# gigafoc.net
KiCad netlist of a schematic drawn in EAGLE
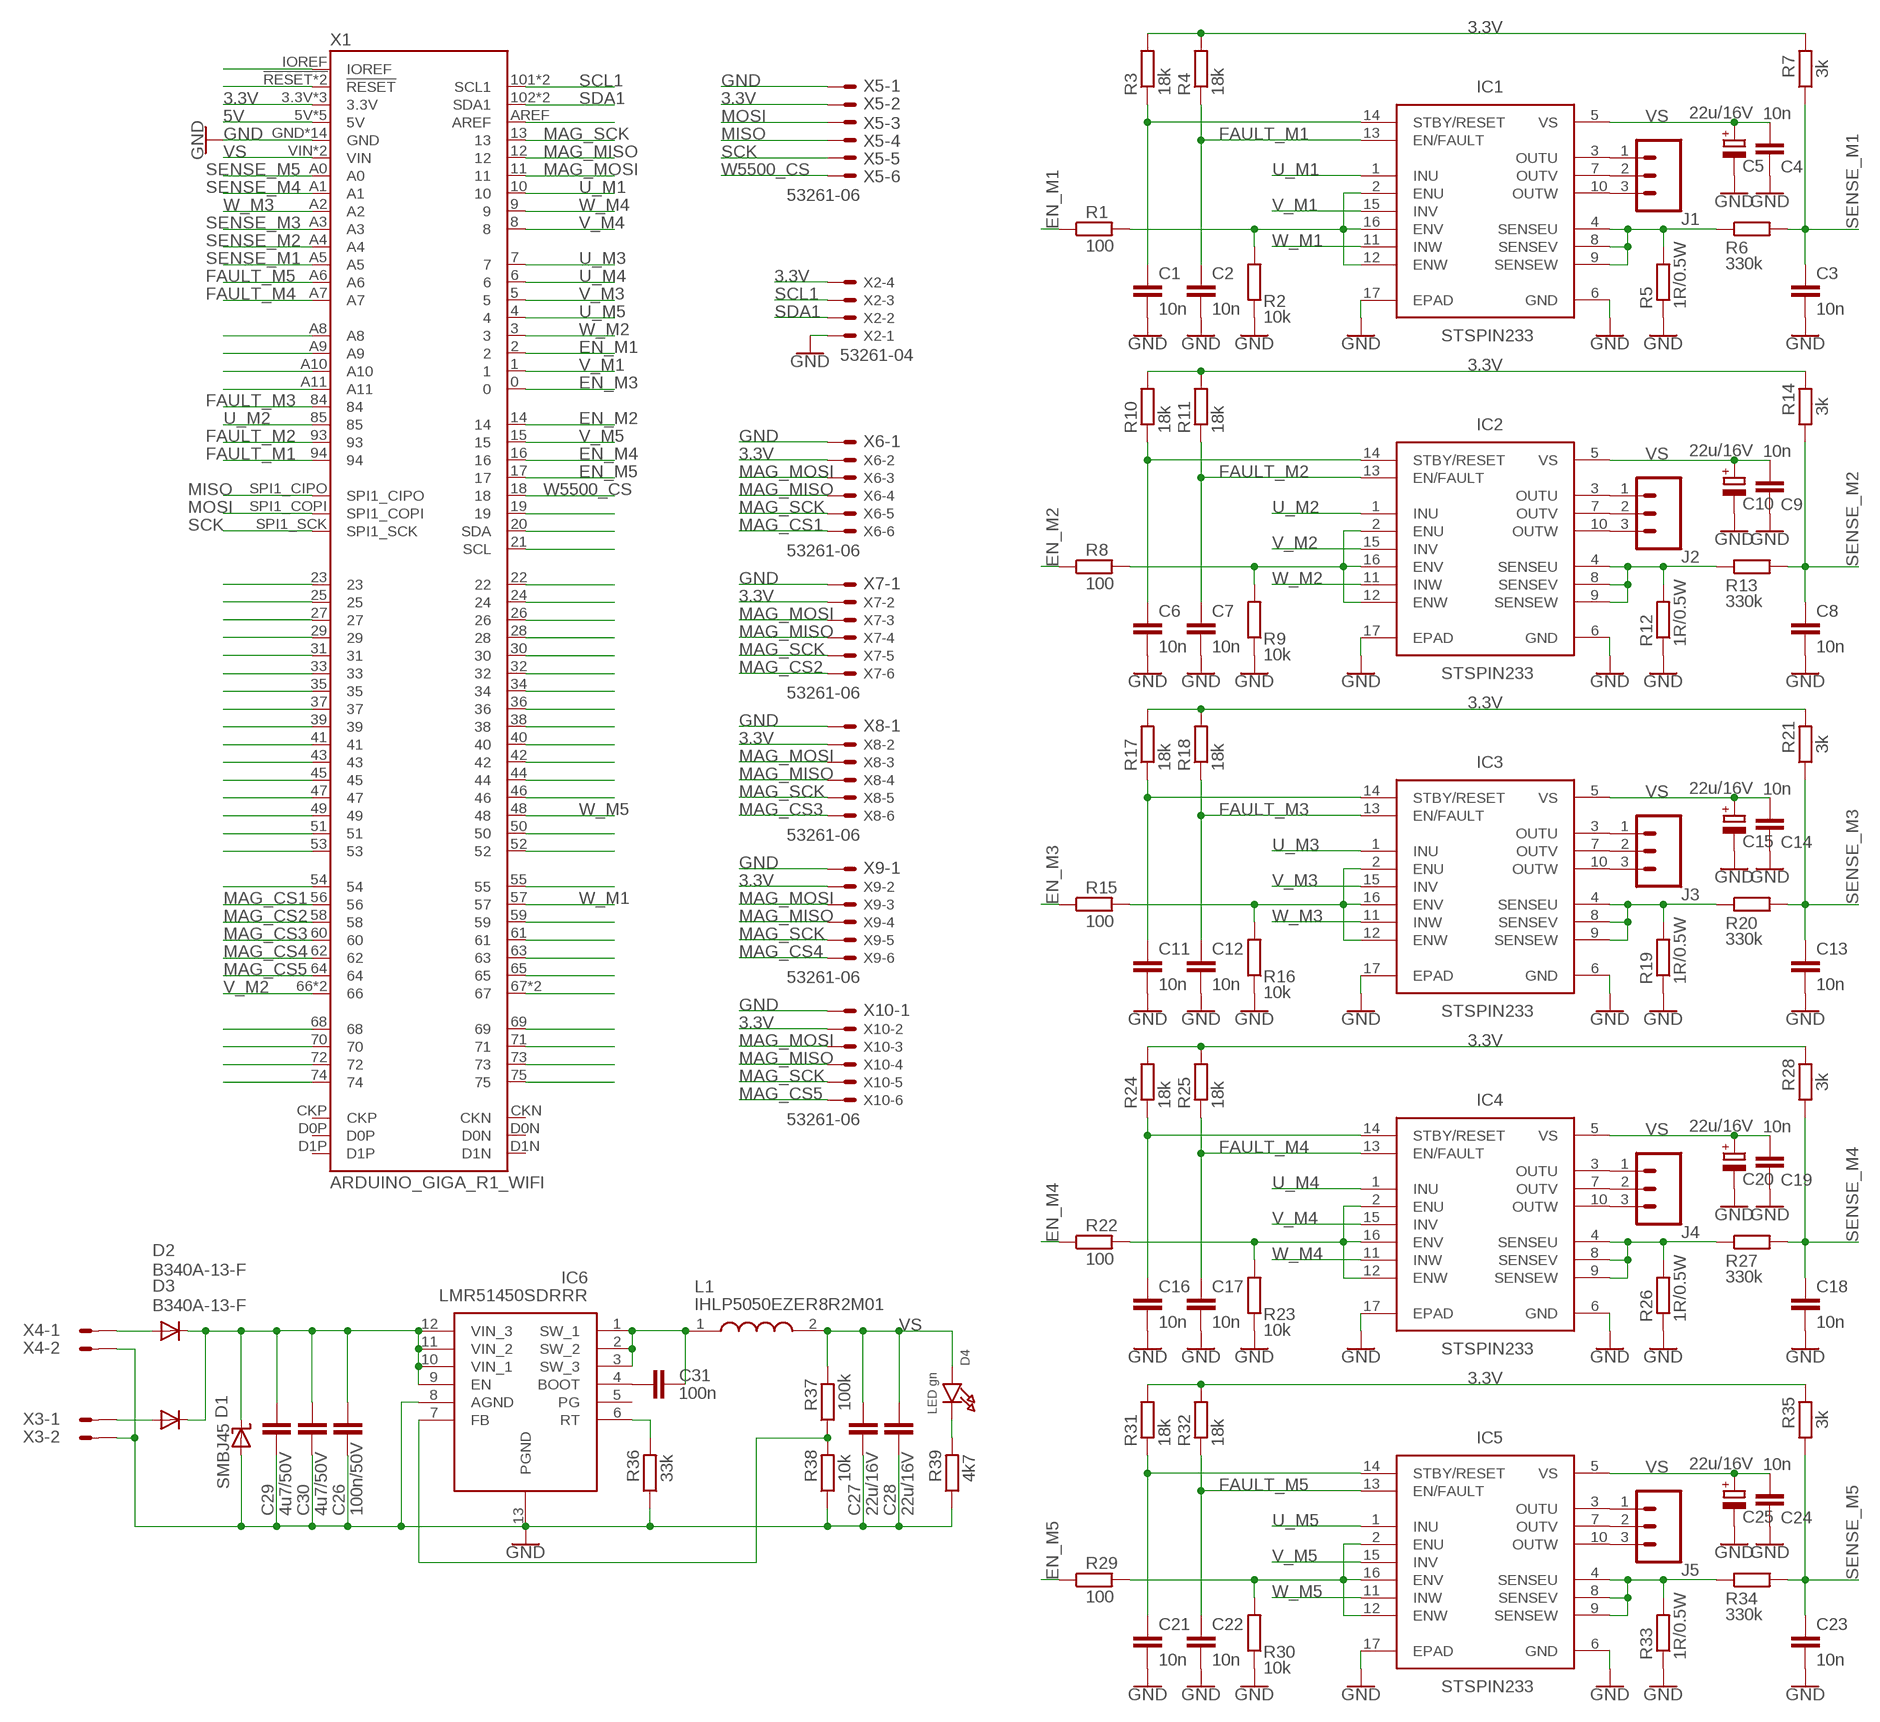
[diagram p0: schematic, sheet 1]

(export (version "E")
  (design (tool "Eeschema 10.0.6"))
  (components
    (comp (ref "C1")
      (value "10n")
      (footprint "eagle-import:C0603")
      (libsource (lib "eagle-import") (part "C-EUC0603"))
    )
    (comp (ref "C2")
      (value "10n")
      (footprint "eagle-import:C0603")
      (libsource (lib "eagle-import") (part "C-EUC0603"))
    )
    (comp (ref "C3")
      (value "10n")
      (footprint "eagle-import:C0603")
      (libsource (lib "eagle-import") (part "C-EUC0603"))
    )
    (comp (ref "C4")
      (value "10n")
      (footprint "eagle-import:C0603")
      (libsource (lib "eagle-import") (part "C-EUC0603"))
    )
    (comp (ref "C5")
      (value "22u/16V")
      (footprint "eagle-import:SMC_B")
      (libsource (lib "eagle-import") (part "CPOL-EUSMCB"))
    )
    (comp (ref "C6")
      (value "10n")
      (footprint "eagle-import:C0603")
      (libsource (lib "eagle-import") (part "C-EUC0603"))
    )
    (comp (ref "C7")
      (value "10n")
      (footprint "eagle-import:C0603")
      (libsource (lib "eagle-import") (part "C-EUC0603"))
    )
    (comp (ref "C8")
      (value "10n")
      (footprint "eagle-import:C0603")
      (libsource (lib "eagle-import") (part "C-EUC0603"))
    )
    (comp (ref "C9")
      (value "10n")
      (footprint "eagle-import:C0603")
      (libsource (lib "eagle-import") (part "C-EUC0603"))
    )
    (comp (ref "C10")
      (value "22u/16V")
      (footprint "eagle-import:SMC_B")
      (libsource (lib "eagle-import") (part "CPOL-EUSMCB"))
    )
    (comp (ref "C11")
      (value "10n")
      (footprint "eagle-import:C0603")
      (libsource (lib "eagle-import") (part "C-EUC0603"))
    )
    (comp (ref "C12")
      (value "10n")
      (footprint "eagle-import:C0603")
      (libsource (lib "eagle-import") (part "C-EUC0603"))
    )
    (comp (ref "C13")
      (value "10n")
      (footprint "eagle-import:C0603")
      (libsource (lib "eagle-import") (part "C-EUC0603"))
    )
    (comp (ref "C14")
      (value "10n")
      (footprint "eagle-import:C0603")
      (libsource (lib "eagle-import") (part "C-EUC0603"))
    )
    (comp (ref "C15")
      (value "22u/16V")
      (footprint "eagle-import:SMC_B")
      (libsource (lib "eagle-import") (part "CPOL-EUSMCB"))
    )
    (comp (ref "C16")
      (value "10n")
      (footprint "eagle-import:C0603")
      (libsource (lib "eagle-import") (part "C-EUC0603"))
    )
    (comp (ref "C17")
      (value "10n")
      (footprint "eagle-import:C0603")
      (libsource (lib "eagle-import") (part "C-EUC0603"))
    )
    (comp (ref "C18")
      (value "10n")
      (footprint "eagle-import:C0603")
      (libsource (lib "eagle-import") (part "C-EUC0603"))
    )
    (comp (ref "C19")
      (value "10n")
      (footprint "eagle-import:C0603")
      (libsource (lib "eagle-import") (part "C-EUC0603"))
    )
    (comp (ref "C20")
      (value "22u/16V")
      (footprint "eagle-import:SMC_B")
      (libsource (lib "eagle-import") (part "CPOL-EUSMCB"))
    )
    (comp (ref "C21")
      (value "10n")
      (footprint "eagle-import:C0603")
      (libsource (lib "eagle-import") (part "C-EUC0603"))
    )
    (comp (ref "C22")
      (value "10n")
      (footprint "eagle-import:C0603")
      (libsource (lib "eagle-import") (part "C-EUC0603"))
    )
    (comp (ref "C23")
      (value "10n")
      (footprint "eagle-import:C0603")
      (libsource (lib "eagle-import") (part "C-EUC0603"))
    )
    (comp (ref "C24")
      (value "10n")
      (footprint "eagle-import:C0603")
      (libsource (lib "eagle-import") (part "C-EUC0603"))
    )
    (comp (ref "C25")
      (value "22u/16V")
      (footprint "eagle-import:SMC_B")
      (libsource (lib "eagle-import") (part "CPOL-EUSMCB"))
    )
    (comp (ref "C26")
      (value "100n/50V")
      (footprint "eagle-import:C0805")
      (libsource (lib "eagle-import") (part "C-EUC0805"))
    )
    (comp (ref "C27")
      (value "22u/16V")
      (footprint "eagle-import:C1210")
      (libsource (lib "eagle-import") (part "C-EUC1210"))
    )
    (comp (ref "C28")
      (value "22u/16V")
      (footprint "eagle-import:C1210")
      (libsource (lib "eagle-import") (part "C-EUC1210"))
    )
    (comp (ref "C29")
      (value "4u7/50V")
      (footprint "eagle-import:C1210K")
      (libsource (lib "eagle-import") (part "C-EUC1210K"))
    )
    (comp (ref "C30")
      (value "4u7/50V")
      (footprint "eagle-import:C1210K")
      (libsource (lib "eagle-import") (part "C-EUC1210K"))
    )
    (comp (ref "C31")
      (value "100n")
      (footprint "eagle-import:C0603")
      (libsource (lib "eagle-import") (part "C-EUC0603"))
    )
    (comp (ref "D1")
      (value "SMBJ45")
      (footprint "eagle-import:SMBJ")
      (libsource (lib "eagle-import") (part "SUPPRESSOR-SMBJ"))
    )
    (comp (ref "D2")
      (value "B340A-13-F")
      (footprint "eagle-import:DO214AC")
      (libsource (lib "eagle-import") (part "DIODE-DO214AC"))
    )
    (comp (ref "D3")
      (value "B340A-13-F")
      (footprint "eagle-import:DO214AC")
      (libsource (lib "eagle-import") (part "DIODE-DO214AC"))
    )
    (comp (ref "D4")
      (value "LED gn")
      (footprint "eagle-import:CHIPLED_0603_NOOUTLINE")
      (libsource (lib "eagle-import") (part "LED0603_NOOUTLINE"))
    )
    (comp (ref "IC1")
      (value "STSPIN233")
      (footprint "eagle-import:QFN50P300X300X100-17N")
      (fields (field (name "MOUSER_PART_NUMBER") "511-STSPIN233"))
      (libsource (lib "eagle-import") (part "STSPIN233"))
    )
    (comp (ref "IC2")
      (value "STSPIN233")
      (footprint "eagle-import:QFN50P300X300X100-17N")
      (fields (field (name "MOUSER_PART_NUMBER") "511-STSPIN233"))
      (libsource (lib "eagle-import") (part "STSPIN233"))
    )
    (comp (ref "IC3")
      (value "STSPIN233")
      (footprint "eagle-import:QFN50P300X300X100-17N")
      (fields (field (name "MOUSER_PART_NUMBER") "511-STSPIN233"))
      (libsource (lib "eagle-import") (part "STSPIN233"))
    )
    (comp (ref "IC4")
      (value "STSPIN233")
      (footprint "eagle-import:QFN50P300X300X100-17N")
      (fields (field (name "MOUSER_PART_NUMBER") "511-STSPIN233"))
      (libsource (lib "eagle-import") (part "STSPIN233"))
    )
    (comp (ref "IC5")
      (value "STSPIN233")
      (footprint "eagle-import:QFN50P300X300X100-17N")
      (fields (field (name "MOUSER_PART_NUMBER") "511-STSPIN233"))
      (libsource (lib "eagle-import") (part "STSPIN233"))
    )
    (comp (ref "IC6")
      (value "LMR51450SDRRR")
      (footprint "eagle-import:SON50P300X300X80-13N")
      (fields (field (name "MOUSER_PART_NUMBER") "595-LMR51450SDRRR"))
      (libsource (lib "eagle-import") (part "LMR51450SDRRR"))
    )
    (comp (ref "J1")
      (value "CONN_03POLAR")
      (footprint "eagle-import:MOLEX-1X3")
      (libsource (lib "eagle-import") (part "CONN_03POLAR"))
    )
    (comp (ref "J2")
      (value "CONN_03POLAR")
      (footprint "eagle-import:MOLEX-1X3")
      (libsource (lib "eagle-import") (part "CONN_03POLAR"))
    )
    (comp (ref "J3")
      (value "CONN_03POLAR")
      (footprint "eagle-import:MOLEX-1X3")
      (libsource (lib "eagle-import") (part "CONN_03POLAR"))
    )
    (comp (ref "J4")
      (value "CONN_03POLAR")
      (footprint "eagle-import:MOLEX-1X3")
      (libsource (lib "eagle-import") (part "CONN_03POLAR"))
    )
    (comp (ref "J5")
      (value "CONN_03POLAR")
      (footprint "eagle-import:MOLEX-1X3")
      (libsource (lib "eagle-import") (part "CONN_03POLAR"))
    )
    (comp (ref "L1")
      (value "IHLP5050EZER8R2M01")
      (footprint "eagle-import:INDPM132129X500N")
      (fields (field (name "MOUSER_PART_NUMBER") "70-IHLP5050EZER8R2M1"))
      (libsource (lib "eagle-import") (part "IHLP5050EZER8R2M01"))
    )
    (comp (ref "R1")
      (value "100")
      (footprint "eagle-import:R0603")
      (libsource (lib "eagle-import") (part "R-EU_R0603"))
    )
    (comp (ref "R2")
      (value "10k")
      (footprint "eagle-import:R0603")
      (libsource (lib "eagle-import") (part "R-EU_R0603"))
    )
    (comp (ref "R3")
      (value "18k")
      (footprint "eagle-import:R0603")
      (libsource (lib "eagle-import") (part "R-EU_R0603"))
    )
    (comp (ref "R4")
      (value "18k")
      (footprint "eagle-import:R0603")
      (libsource (lib "eagle-import") (part "R-EU_R0603"))
    )
    (comp (ref "R5")
      (value "1R/0.5W")
      (footprint "eagle-import:R1206")
      (libsource (lib "eagle-import") (part "R-EU_R1206"))
    )
    (comp (ref "R6")
      (value "330k")
      (footprint "eagle-import:R0603")
      (libsource (lib "eagle-import") (part "R-EU_R0603"))
    )
    (comp (ref "R7")
      (value "3k")
      (footprint "eagle-import:R0603")
      (libsource (lib "eagle-import") (part "R-EU_R0603"))
    )
    (comp (ref "R8")
      (value "100")
      (footprint "eagle-import:R0603")
      (libsource (lib "eagle-import") (part "R-EU_R0603"))
    )
    (comp (ref "R9")
      (value "10k")
      (footprint "eagle-import:R0603")
      (libsource (lib "eagle-import") (part "R-EU_R0603"))
    )
    (comp (ref "R10")
      (value "18k")
      (footprint "eagle-import:R0603")
      (libsource (lib "eagle-import") (part "R-EU_R0603"))
    )
    (comp (ref "R11")
      (value "18k")
      (footprint "eagle-import:R0603")
      (libsource (lib "eagle-import") (part "R-EU_R0603"))
    )
    (comp (ref "R12")
      (value "1R/0.5W")
      (footprint "eagle-import:R1206")
      (libsource (lib "eagle-import") (part "R-EU_R1206"))
    )
    (comp (ref "R13")
      (value "330k")
      (footprint "eagle-import:R0603")
      (libsource (lib "eagle-import") (part "R-EU_R0603"))
    )
    (comp (ref "R14")
      (value "3k")
      (footprint "eagle-import:R0603")
      (libsource (lib "eagle-import") (part "R-EU_R0603"))
    )
    (comp (ref "R15")
      (value "100")
      (footprint "eagle-import:R0603")
      (libsource (lib "eagle-import") (part "R-EU_R0603"))
    )
    (comp (ref "R16")
      (value "10k")
      (footprint "eagle-import:R0603")
      (libsource (lib "eagle-import") (part "R-EU_R0603"))
    )
    (comp (ref "R17")
      (value "18k")
      (footprint "eagle-import:R0603")
      (libsource (lib "eagle-import") (part "R-EU_R0603"))
    )
    (comp (ref "R18")
      (value "18k")
      (footprint "eagle-import:R0603")
      (libsource (lib "eagle-import") (part "R-EU_R0603"))
    )
    (comp (ref "R19")
      (value "1R/0.5W")
      (footprint "eagle-import:R1206")
      (libsource (lib "eagle-import") (part "R-EU_R1206"))
    )
    (comp (ref "R20")
      (value "330k")
      (footprint "eagle-import:R0603")
      (libsource (lib "eagle-import") (part "R-EU_R0603"))
    )
    (comp (ref "R21")
      (value "3k")
      (footprint "eagle-import:R0603")
      (libsource (lib "eagle-import") (part "R-EU_R0603"))
    )
    (comp (ref "R22")
      (value "100")
      (footprint "eagle-import:R0603")
      (libsource (lib "eagle-import") (part "R-EU_R0603"))
    )
    (comp (ref "R23")
      (value "10k")
      (footprint "eagle-import:R0603")
      (libsource (lib "eagle-import") (part "R-EU_R0603"))
    )
    (comp (ref "R24")
      (value "18k")
      (footprint "eagle-import:R0603")
      (libsource (lib "eagle-import") (part "R-EU_R0603"))
    )
    (comp (ref "R25")
      (value "18k")
      (footprint "eagle-import:R0603")
      (libsource (lib "eagle-import") (part "R-EU_R0603"))
    )
    (comp (ref "R26")
      (value "1R/0.5W")
      (footprint "eagle-import:R1206")
      (libsource (lib "eagle-import") (part "R-EU_R1206"))
    )
    (comp (ref "R27")
      (value "330k")
      (footprint "eagle-import:R0603")
      (libsource (lib "eagle-import") (part "R-EU_R0603"))
    )
    (comp (ref "R28")
      (value "3k")
      (footprint "eagle-import:R0603")
      (libsource (lib "eagle-import") (part "R-EU_R0603"))
    )
    (comp (ref "R29")
      (value "100")
      (footprint "eagle-import:R0603")
      (libsource (lib "eagle-import") (part "R-EU_R0603"))
    )
    (comp (ref "R30")
      (value "10k")
      (footprint "eagle-import:R0603")
      (libsource (lib "eagle-import") (part "R-EU_R0603"))
    )
    (comp (ref "R31")
      (value "18k")
      (footprint "eagle-import:R0603")
      (libsource (lib "eagle-import") (part "R-EU_R0603"))
    )
    (comp (ref "R32")
      (value "18k")
      (footprint "eagle-import:R0603")
      (libsource (lib "eagle-import") (part "R-EU_R0603"))
    )
    (comp (ref "R33")
      (value "1R/0.5W")
      (footprint "eagle-import:R1206")
      (libsource (lib "eagle-import") (part "R-EU_R1206"))
    )
    (comp (ref "R34")
      (value "330k")
      (footprint "eagle-import:R0603")
      (libsource (lib "eagle-import") (part "R-EU_R0603"))
    )
    (comp (ref "R35")
      (value "3k")
      (footprint "eagle-import:R0603")
      (libsource (lib "eagle-import") (part "R-EU_R0603"))
    )
    (comp (ref "R36")
      (value "33k")
      (footprint "eagle-import:R0603")
      (libsource (lib "eagle-import") (part "R-EU_R0603"))
    )
    (comp (ref "R37")
      (value "100k")
      (footprint "eagle-import:R0603")
      (libsource (lib "eagle-import") (part "R-EU_R0603"))
    )
    (comp (ref "R38")
      (value "10k")
      (footprint "eagle-import:R0603")
      (libsource (lib "eagle-import") (part "R-EU_R0603"))
    )
    (comp (ref "R39")
      (value "4k7")
      (footprint "eagle-import:R0603")
      (libsource (lib "eagle-import") (part "R-EU_R0603"))
    )
    (comp (ref "X1")
      (value "ARDUINO_GIGA_R1_WIFI")
      (footprint "eagle-import:ARDUINO_GIGA_NO_SILK")
      (libsource (lib "eagle-import") (part "ARDUINO_GIGA_R1_WIFI"))
    )
    (comp (ref "X2")
      (value "53261-04")
      (footprint "eagle-import:53261-04")
      (fields (field (name "MF") "MOLEX"))
      (libsource (lib "eagle-import") (part "53?-04261"))
    )
    (comp (ref "X3")
      (value "S02P")
      (footprint "eagle-import:S02P")
      (libsource (lib "eagle-import") (part "S02P"))
    )
    (comp (ref "X4")
      (value "S02P")
      (footprint "eagle-import:S02P")
      (libsource (lib "eagle-import") (part "S02P"))
    )
    (comp (ref "X5")
      (value "53261-06")
      (footprint "eagle-import:53261-06")
      (fields (field (name "MF") "MOLEX"))
      (libsource (lib "eagle-import") (part "53?-06261"))
    )
    (comp (ref "X6")
      (value "53261-06")
      (footprint "eagle-import:53261-06")
      (fields (field (name "MF") "MOLEX"))
      (libsource (lib "eagle-import") (part "53?-06261"))
    )
    (comp (ref "X7")
      (value "53261-06")
      (footprint "eagle-import:53261-06")
      (fields (field (name "MF") "MOLEX"))
      (libsource (lib "eagle-import") (part "53?-06261"))
    )
    (comp (ref "X8")
      (value "53261-06")
      (footprint "eagle-import:53261-06")
      (fields (field (name "MF") "MOLEX"))
      (libsource (lib "eagle-import") (part "53?-06261"))
    )
    (comp (ref "X9")
      (value "53261-06")
      (footprint "eagle-import:53261-06")
      (fields (field (name "MF") "MOLEX"))
      (libsource (lib "eagle-import") (part "53?-06261"))
    )
    (comp (ref "X10")
      (value "53261-06")
      (footprint "eagle-import:53261-06")
      (fields (field (name "MF") "MOLEX"))
      (libsource (lib "eagle-import") (part "53?-06261"))
    )
  )
  (nets
    (net (code "1") (name "/3.3V") (class "Default")
      (node (ref "R10") (pin "2") (pinfunction "2_2") (pintype "passive"))
      (node (ref "R11") (pin "2") (pinfunction "2_2") (pintype "passive"))
      (node (ref "R14") (pin "2") (pinfunction "2_2") (pintype "passive"))
      (node (ref "R17") (pin "2") (pinfunction "2_2") (pintype "passive"))
      (node (ref "R18") (pin "2") (pinfunction "2_2") (pintype "passive"))
      (node (ref "R21") (pin "2") (pinfunction "2_2") (pintype "passive"))
      (node (ref "R24") (pin "2") (pinfunction "2_2") (pintype "passive"))
      (node (ref "R25") (pin "2") (pinfunction "2_2") (pintype "passive"))
      (node (ref "R28") (pin "2") (pinfunction "2_2") (pintype "passive"))
      (node (ref "R3") (pin "2") (pinfunction "2_2") (pintype "passive"))
      (node (ref "R31") (pin "2") (pinfunction "2_2") (pintype "passive"))
      (node (ref "R32") (pin "2") (pinfunction "2_2") (pintype "passive"))
      (node (ref "R35") (pin "2") (pinfunction "2_2") (pintype "passive"))
      (node (ref "R4") (pin "2") (pinfunction "2_2") (pintype "passive"))
      (node (ref "R7") (pin "2") (pinfunction "2_2") (pintype "passive"))
      (node (ref "X1") (pin "3.3V") (pinfunction "3.3V_3.3V") (pintype "bidirectional"))
      (node (ref "X1") (pin "3.3V@1") (pinfunction "3.3V_3.3V@1") (pintype "bidirectional"))
      (node (ref "X1") (pin "3.3V@2") (pinfunction "3.3V_3.3V@2") (pintype "bidirectional"))
      (node (ref "X10") (pin "2") (pinfunction "S_2") (pintype "passive"))
      (node (ref "X2") (pin "4") (pinfunction "S_4") (pintype "passive"))
      (node (ref "X5") (pin "2") (pinfunction "S_2") (pintype "passive"))
      (node (ref "X6") (pin "2") (pinfunction "S_2") (pintype "passive"))
      (node (ref "X7") (pin "2") (pinfunction "S_2") (pintype "passive"))
      (node (ref "X8") (pin "2") (pinfunction "S_2") (pintype "passive"))
      (node (ref "X9") (pin "2") (pinfunction "S_2") (pintype "passive"))
    )
    (net (code "2") (name "/5V") (class "Default")
      (node (ref "X1") (pin "5V") (pinfunction "5V_5V") (pintype "bidirectional"))
      (node (ref "X1") (pin "5V@1") (pinfunction "5V_5V@1") (pintype "bidirectional"))
      (node (ref "X1") (pin "5V@2") (pinfunction "5V_5V@2") (pintype "bidirectional"))
      (node (ref "X1") (pin "5V@3") (pinfunction "5V_5V@3") (pintype "bidirectional"))
      (node (ref "X1") (pin "5V@4") (pinfunction "5V_5V@4") (pintype "bidirectional"))
    )
    (net (code "3") (name "/EN_M1") (class "Default")
      (node (ref "R1") (pin "1") (pinfunction "1_1") (pintype "passive"))
      (node (ref "X1") (pin "2") (pinfunction "2_2") (pintype "bidirectional"))
    )
    (net (code "4") (name "/EN_M2") (class "Default")
      (node (ref "R8") (pin "1") (pinfunction "1_1") (pintype "passive"))
      (node (ref "X1") (pin "14") (pinfunction "14_14") (pintype "bidirectional"))
    )
    (net (code "5") (name "/EN_M3") (class "Default")
      (node (ref "R15") (pin "1") (pinfunction "1_1") (pintype "passive"))
      (node (ref "X1") (pin "0") (pinfunction "0_0") (pintype "bidirectional"))
    )
    (net (code "6") (name "/EN_M4") (class "Default")
      (node (ref "R22") (pin "1") (pinfunction "1_1") (pintype "passive"))
      (node (ref "X1") (pin "16") (pinfunction "16_16") (pintype "bidirectional"))
    )
    (net (code "7") (name "/EN_M5") (class "Default")
      (node (ref "R29") (pin "1") (pinfunction "1_1") (pintype "passive"))
      (node (ref "X1") (pin "17") (pinfunction "17_17") (pintype "bidirectional"))
    )
    (net (code "8") (name "/FAULT_M1") (class "Default")
      (node (ref "C2") (pin "2") (pinfunction "2_2") (pintype "passive"))
      (node (ref "IC1") (pin "13") (pinfunction "EN/FAULT_13") (pintype "bidirectional"))
      (node (ref "R4") (pin "1") (pinfunction "1_1") (pintype "passive"))
      (node (ref "X1") (pin "94") (pinfunction "94_94") (pintype "bidirectional"))
    )
    (net (code "9") (name "/FAULT_M2") (class "Default")
      (node (ref "C7") (pin "2") (pinfunction "2_2") (pintype "passive"))
      (node (ref "IC2") (pin "13") (pinfunction "EN/FAULT_13") (pintype "bidirectional"))
      (node (ref "R11") (pin "1") (pinfunction "1_1") (pintype "passive"))
      (node (ref "X1") (pin "93") (pinfunction "93_93") (pintype "bidirectional"))
    )
    (net (code "10") (name "/FAULT_M3") (class "Default")
      (node (ref "C12") (pin "2") (pinfunction "2_2") (pintype "passive"))
      (node (ref "IC3") (pin "13") (pinfunction "EN/FAULT_13") (pintype "bidirectional"))
      (node (ref "R18") (pin "1") (pinfunction "1_1") (pintype "passive"))
      (node (ref "X1") (pin "84") (pinfunction "84_84") (pintype "bidirectional"))
    )
    (net (code "11") (name "/FAULT_M4") (class "Default")
      (node (ref "C17") (pin "2") (pinfunction "2_2") (pintype "passive"))
      (node (ref "IC4") (pin "13") (pinfunction "EN/FAULT_13") (pintype "bidirectional"))
      (node (ref "R25") (pin "1") (pinfunction "1_1") (pintype "passive"))
      (node (ref "X1") (pin "A7") (pinfunction "A7_A7") (pintype "bidirectional"))
    )
    (net (code "12") (name "/FAULT_M5") (class "Default")
      (node (ref "C22") (pin "2") (pinfunction "2_2") (pintype "passive"))
      (node (ref "IC5") (pin "13") (pinfunction "EN/FAULT_13") (pintype "bidirectional"))
      (node (ref "R32") (pin "1") (pinfunction "1_1") (pintype "passive"))
      (node (ref "X1") (pin "A6") (pinfunction "A6_A6") (pintype "bidirectional"))
    )
    (net (code "13") (name "/MAG_CS1") (class "Default")
      (node (ref "X1") (pin "56") (pinfunction "56_56") (pintype "bidirectional"))
      (node (ref "X6") (pin "6") (pinfunction "S_6") (pintype "passive"))
    )
    (net (code "14") (name "/MAG_CS2") (class "Default")
      (node (ref "X1") (pin "58") (pinfunction "58_58") (pintype "bidirectional"))
      (node (ref "X7") (pin "6") (pinfunction "S_6") (pintype "passive"))
    )
    (net (code "15") (name "/MAG_CS3") (class "Default")
      (node (ref "X1") (pin "60") (pinfunction "60_60") (pintype "bidirectional"))
      (node (ref "X8") (pin "6") (pinfunction "S_6") (pintype "passive"))
    )
    (net (code "16") (name "/MAG_CS4") (class "Default")
      (node (ref "X1") (pin "62") (pinfunction "62_62") (pintype "bidirectional"))
      (node (ref "X9") (pin "6") (pinfunction "S_6") (pintype "passive"))
    )
    (net (code "17") (name "/MAG_CS5") (class "Default")
      (node (ref "X1") (pin "64") (pinfunction "64_64") (pintype "bidirectional"))
      (node (ref "X10") (pin "6") (pinfunction "S_6") (pintype "passive"))
    )
    (net (code "18") (name "/MAG_MISO") (class "Default")
      (node (ref "X1") (pin "12") (pinfunction "12_12") (pintype "bidirectional"))
      (node (ref "X10") (pin "4") (pinfunction "S_4") (pintype "passive"))
      (node (ref "X6") (pin "4") (pinfunction "S_4") (pintype "passive"))
      (node (ref "X7") (pin "4") (pinfunction "S_4") (pintype "passive"))
      (node (ref "X8") (pin "4") (pinfunction "S_4") (pintype "passive"))
      (node (ref "X9") (pin "4") (pinfunction "S_4") (pintype "passive"))
    )
    (net (code "19") (name "/MAG_MOSI") (class "Default")
      (node (ref "X1") (pin "11") (pinfunction "11_11") (pintype "bidirectional"))
      (node (ref "X10") (pin "3") (pinfunction "S_3") (pintype "passive"))
      (node (ref "X6") (pin "3") (pinfunction "S_3") (pintype "passive"))
      (node (ref "X7") (pin "3") (pinfunction "S_3") (pintype "passive"))
      (node (ref "X8") (pin "3") (pinfunction "S_3") (pintype "passive"))
      (node (ref "X9") (pin "3") (pinfunction "S_3") (pintype "passive"))
    )
    (net (code "20") (name "/MAG_SCK") (class "Default")
      (node (ref "X1") (pin "13") (pinfunction "13_13") (pintype "bidirectional"))
      (node (ref "X10") (pin "5") (pinfunction "S_5") (pintype "passive"))
      (node (ref "X6") (pin "5") (pinfunction "S_5") (pintype "passive"))
      (node (ref "X7") (pin "5") (pinfunction "S_5") (pintype "passive"))
      (node (ref "X8") (pin "5") (pinfunction "S_5") (pintype "passive"))
      (node (ref "X9") (pin "5") (pinfunction "S_5") (pintype "passive"))
    )
    (net (code "21") (name "/MISO") (class "Default")
      (node (ref "X1") (pin "SPI1_CIPO") (pinfunction "SPI1_CIPO_SPI1_CIPO") (pintype "bidirectional"))
      (node (ref "X5") (pin "4") (pinfunction "S_4") (pintype "passive"))
    )
    (net (code "22") (name "/MOSI") (class "Default")
      (node (ref "X1") (pin "SPI1_COPI") (pinfunction "SPI1_COPI_SPI1_COPI") (pintype "bidirectional"))
      (node (ref "X5") (pin "3") (pinfunction "S_3") (pintype "passive"))
    )
    (net (code "23") (name "/SCK") (class "Default")
      (node (ref "X1") (pin "SPI1_SCK") (pinfunction "SPI1_SCK_SPI1_SCK") (pintype "bidirectional"))
      (node (ref "X5") (pin "5") (pinfunction "S_5") (pintype "passive"))
    )
    (net (code "24") (name "/SCL1") (class "Default")
      (node (ref "X1") (pin "101") (pinfunction "SCL1_101") (pintype "bidirectional"))
      (node (ref "X1") (pin "101@1") (pinfunction "SCL1_101@1") (pintype "bidirectional"))
      (node (ref "X2") (pin "3") (pinfunction "S_3") (pintype "passive"))
    )
    (net (code "25") (name "/SDA1") (class "Default")
      (node (ref "X1") (pin "102") (pinfunction "SDA1_102") (pintype "bidirectional"))
      (node (ref "X1") (pin "102@1") (pinfunction "SDA1_102@1") (pintype "bidirectional"))
      (node (ref "X2") (pin "2") (pinfunction "S_2") (pintype "passive"))
    )
    (net (code "26") (name "/SENSE_M1") (class "Default")
      (node (ref "C3") (pin "2") (pinfunction "2_2") (pintype "passive"))
      (node (ref "R6") (pin "2") (pinfunction "2_2") (pintype "passive"))
      (node (ref "R7") (pin "1") (pinfunction "1_1") (pintype "passive"))
      (node (ref "X1") (pin "A5") (pinfunction "A5_A5") (pintype "bidirectional"))
    )
    (net (code "27") (name "/SENSE_M2") (class "Default")
      (node (ref "C8") (pin "2") (pinfunction "2_2") (pintype "passive"))
      (node (ref "R13") (pin "2") (pinfunction "2_2") (pintype "passive"))
      (node (ref "R14") (pin "1") (pinfunction "1_1") (pintype "passive"))
      (node (ref "X1") (pin "A4") (pinfunction "A4_A4") (pintype "bidirectional"))
    )
    (net (code "28") (name "/SENSE_M3") (class "Default")
      (node (ref "C13") (pin "2") (pinfunction "2_2") (pintype "passive"))
      (node (ref "R20") (pin "2") (pinfunction "2_2") (pintype "passive"))
      (node (ref "R21") (pin "1") (pinfunction "1_1") (pintype "passive"))
      (node (ref "X1") (pin "A3") (pinfunction "A3_A3") (pintype "bidirectional"))
    )
    (net (code "29") (name "/SENSE_M4") (class "Default")
      (node (ref "C18") (pin "2") (pinfunction "2_2") (pintype "passive"))
      (node (ref "R27") (pin "2") (pinfunction "2_2") (pintype "passive"))
      (node (ref "R28") (pin "1") (pinfunction "1_1") (pintype "passive"))
      (node (ref "X1") (pin "A1") (pinfunction "A1_A1") (pintype "bidirectional"))
    )
    (net (code "30") (name "/SENSE_M5") (class "Default")
      (node (ref "C23") (pin "2") (pinfunction "2_2") (pintype "passive"))
      (node (ref "R34") (pin "2") (pinfunction "2_2") (pintype "passive"))
      (node (ref "R35") (pin "1") (pinfunction "1_1") (pintype "passive"))
      (node (ref "X1") (pin "A0") (pinfunction "A0_A0") (pintype "bidirectional"))
    )
    (net (code "31") (name "/U_M1") (class "Default")
      (node (ref "IC1") (pin "1") (pinfunction "INU_1") (pintype "bidirectional"))
      (node (ref "X1") (pin "10") (pinfunction "10_10") (pintype "bidirectional"))
    )
    (net (code "32") (name "/U_M2") (class "Default")
      (node (ref "IC2") (pin "1") (pinfunction "INU_1") (pintype "bidirectional"))
      (node (ref "X1") (pin "85") (pinfunction "85_85") (pintype "bidirectional"))
    )
    (net (code "33") (name "/U_M3") (class "Default")
      (node (ref "IC3") (pin "1") (pinfunction "INU_1") (pintype "bidirectional"))
      (node (ref "X1") (pin "7") (pinfunction "7_7") (pintype "bidirectional"))
    )
    (net (code "34") (name "/U_M4") (class "Default")
      (node (ref "IC4") (pin "1") (pinfunction "INU_1") (pintype "bidirectional"))
      (node (ref "X1") (pin "6") (pinfunction "6_6") (pintype "bidirectional"))
    )
    (net (code "35") (name "/U_M5") (class "Default")
      (node (ref "IC5") (pin "1") (pinfunction "INU_1") (pintype "bidirectional"))
      (node (ref "X1") (pin "4") (pinfunction "4_4") (pintype "bidirectional"))
    )
    (net (code "36") (name "/VS") (class "Default")
      (node (ref "C10") (pin "+") (pinfunction "+_+") (pintype "passive"))
      (node (ref "C14") (pin "2") (pinfunction "2_2") (pintype "passive"))
      (node (ref "C15") (pin "+") (pinfunction "+_+") (pintype "passive"))
      (node (ref "C19") (pin "2") (pinfunction "2_2") (pintype "passive"))
      (node (ref "C20") (pin "+") (pinfunction "+_+") (pintype "passive"))
      (node (ref "C24") (pin "2") (pinfunction "2_2") (pintype "passive"))
      (node (ref "C25") (pin "+") (pinfunction "+_+") (pintype "passive"))
      (node (ref "C27") (pin "1") (pinfunction "1_1") (pintype "passive"))
      (node (ref "C28") (pin "1") (pinfunction "1_1") (pintype "passive"))
      (node (ref "C4") (pin "2") (pinfunction "2_2") (pintype "passive"))
      (node (ref "C5") (pin "+") (pinfunction "+_+") (pintype "passive"))
      (node (ref "C9") (pin "2") (pinfunction "2_2") (pintype "passive"))
      (node (ref "D4") (pin "A") (pinfunction "A_A") (pintype "passive"))
      (node (ref "IC1") (pin "5") (pinfunction "VS_5") (pintype "bidirectional"))
      (node (ref "IC2") (pin "5") (pinfunction "VS_5") (pintype "bidirectional"))
      (node (ref "IC3") (pin "5") (pinfunction "VS_5") (pintype "bidirectional"))
      (node (ref "IC4") (pin "5") (pinfunction "VS_5") (pintype "bidirectional"))
      (node (ref "IC5") (pin "5") (pinfunction "VS_5") (pintype "bidirectional"))
      (node (ref "L1") (pin "2") (pinfunction "2_2") (pintype "bidirectional"))
      (node (ref "R37") (pin "2") (pinfunction "2_2") (pintype "passive"))
      (node (ref "X1") (pin "VIN") (pinfunction "VIN_VIN") (pintype "bidirectional"))
      (node (ref "X1") (pin "VIN@1") (pinfunction "VIN_VIN@1") (pintype "bidirectional"))
    )
    (net (code "37") (name "/V_M1") (class "Default")
      (node (ref "IC1") (pin "15") (pinfunction "INV_15") (pintype "bidirectional"))
      (node (ref "X1") (pin "1") (pinfunction "1_1") (pintype "bidirectional"))
    )
    (net (code "38") (name "/V_M2") (class "Default")
      (node (ref "IC2") (pin "15") (pinfunction "INV_15") (pintype "bidirectional"))
      (node (ref "X1") (pin "66") (pinfunction "66_66") (pintype "bidirectional"))
      (node (ref "X1") (pin "66@1") (pinfunction "66_66@1") (pintype "bidirectional"))
    )
    (net (code "39") (name "/V_M3") (class "Default")
      (node (ref "IC3") (pin "15") (pinfunction "INV_15") (pintype "bidirectional"))
      (node (ref "X1") (pin "5") (pinfunction "5_5") (pintype "bidirectional"))
    )
    (net (code "40") (name "/V_M4") (class "Default")
      (node (ref "IC4") (pin "15") (pinfunction "INV_15") (pintype "bidirectional"))
      (node (ref "X1") (pin "8") (pinfunction "8_8") (pintype "bidirectional"))
    )
    (net (code "41") (name "/V_M5") (class "Default")
      (node (ref "IC5") (pin "15") (pinfunction "INV_15") (pintype "bidirectional"))
      (node (ref "X1") (pin "15") (pinfunction "15_15") (pintype "bidirectional"))
    )
    (net (code "42") (name "/W5500_CS") (class "Default")
      (node (ref "X1") (pin "18") (pinfunction "18_18") (pintype "bidirectional"))
      (node (ref "X5") (pin "6") (pinfunction "S_6") (pintype "passive"))
    )
    (net (code "43") (name "/W_M1") (class "Default")
      (node (ref "IC1") (pin "11") (pinfunction "INW_11") (pintype "bidirectional"))
      (node (ref "X1") (pin "57") (pinfunction "57_57") (pintype "bidirectional"))
    )
    (net (code "44") (name "/W_M2") (class "Default")
      (node (ref "IC2") (pin "11") (pinfunction "INW_11") (pintype "bidirectional"))
      (node (ref "X1") (pin "3") (pinfunction "3_3") (pintype "bidirectional"))
    )
    (net (code "45") (name "/W_M3") (class "Default")
      (node (ref "IC3") (pin "11") (pinfunction "INW_11") (pintype "bidirectional"))
      (node (ref "X1") (pin "A2") (pinfunction "A2_A2") (pintype "bidirectional"))
    )
    (net (code "46") (name "/W_M4") (class "Default")
      (node (ref "IC4") (pin "11") (pinfunction "INW_11") (pintype "bidirectional"))
      (node (ref "X1") (pin "9") (pinfunction "9_9") (pintype "bidirectional"))
    )
    (net (code "47") (name "/W_M5") (class "Default")
      (node (ref "IC5") (pin "11") (pinfunction "INW_11") (pintype "bidirectional"))
      (node (ref "X1") (pin "48") (pinfunction "48_48") (pintype "bidirectional"))
    )
    (net (code "48") (name "GND") (class "Default")
      (node (ref "C1") (pin "1") (pinfunction "1_1") (pintype "passive"))
      (node (ref "C10") (pin "-") (pinfunction "-_-") (pintype "passive"))
      (node (ref "C11") (pin "1") (pinfunction "1_1") (pintype "passive"))
      (node (ref "C12") (pin "1") (pinfunction "1_1") (pintype "passive"))
      (node (ref "C13") (pin "1") (pinfunction "1_1") (pintype "passive"))
      (node (ref "C14") (pin "1") (pinfunction "1_1") (pintype "passive"))
      (node (ref "C15") (pin "-") (pinfunction "-_-") (pintype "passive"))
      (node (ref "C16") (pin "1") (pinfunction "1_1") (pintype "passive"))
      (node (ref "C17") (pin "1") (pinfunction "1_1") (pintype "passive"))
      (node (ref "C18") (pin "1") (pinfunction "1_1") (pintype "passive"))
      (node (ref "C19") (pin "1") (pinfunction "1_1") (pintype "passive"))
      (node (ref "C2") (pin "1") (pinfunction "1_1") (pintype "passive"))
      (node (ref "C20") (pin "-") (pinfunction "-_-") (pintype "passive"))
      (node (ref "C21") (pin "1") (pinfunction "1_1") (pintype "passive"))
      (node (ref "C22") (pin "1") (pinfunction "1_1") (pintype "passive"))
      (node (ref "C23") (pin "1") (pinfunction "1_1") (pintype "passive"))
      (node (ref "C24") (pin "1") (pinfunction "1_1") (pintype "passive"))
      (node (ref "C25") (pin "-") (pinfunction "-_-") (pintype "passive"))
      (node (ref "C26") (pin "2") (pinfunction "2_2") (pintype "passive"))
      (node (ref "C27") (pin "2") (pinfunction "2_2") (pintype "passive"))
      (node (ref "C28") (pin "2") (pinfunction "2_2") (pintype "passive"))
      (node (ref "C29") (pin "2") (pinfunction "2_2") (pintype "passive"))
      (node (ref "C3") (pin "1") (pinfunction "1_1") (pintype "passive"))
      (node (ref "C30") (pin "2") (pinfunction "2_2") (pintype "passive"))
      (node (ref "C4") (pin "1") (pinfunction "1_1") (pintype "passive"))
      (node (ref "C5") (pin "-") (pinfunction "-_-") (pintype "passive"))
      (node (ref "C6") (pin "1") (pinfunction "1_1") (pintype "passive"))
      (node (ref "C7") (pin "1") (pinfunction "1_1") (pintype "passive"))
      (node (ref "C8") (pin "1") (pinfunction "1_1") (pintype "passive"))
      (node (ref "C9") (pin "1") (pinfunction "1_1") (pintype "passive"))
      (node (ref "D1") (pin "A") (pinfunction "A_A") (pintype "passive"))
      (node (ref "IC1") (pin "17") (pinfunction "EPAD_17") (pintype "bidirectional"))
      (node (ref "IC1") (pin "6") (pinfunction "GND_6") (pintype "bidirectional"))
      (node (ref "IC2") (pin "17") (pinfunction "EPAD_17") (pintype "bidirectional"))
      (node (ref "IC2") (pin "6") (pinfunction "GND_6") (pintype "bidirectional"))
      (node (ref "IC3") (pin "17") (pinfunction "EPAD_17") (pintype "bidirectional"))
      (node (ref "IC3") (pin "6") (pinfunction "GND_6") (pintype "bidirectional"))
      (node (ref "IC4") (pin "17") (pinfunction "EPAD_17") (pintype "bidirectional"))
      (node (ref "IC4") (pin "6") (pinfunction "GND_6") (pintype "bidirectional"))
      (node (ref "IC5") (pin "17") (pinfunction "EPAD_17") (pintype "bidirectional"))
      (node (ref "IC5") (pin "6") (pinfunction "GND_6") (pintype "bidirectional"))
      (node (ref "IC6") (pin "13") (pinfunction "PGND_13") (pintype "bidirectional"))
      (node (ref "IC6") (pin "8") (pinfunction "AGND_8") (pintype "bidirectional"))
      (node (ref "R12") (pin "1") (pinfunction "1_1") (pintype "passive"))
      (node (ref "R16") (pin "1") (pinfunction "1_1") (pintype "passive"))
      (node (ref "R19") (pin "1") (pinfunction "1_1") (pintype "passive"))
      (node (ref "R2") (pin "1") (pinfunction "1_1") (pintype "passive"))
      (node (ref "R23") (pin "1") (pinfunction "1_1") (pintype "passive"))
      (node (ref "R26") (pin "1") (pinfunction "1_1") (pintype "passive"))
      (node (ref "R30") (pin "1") (pinfunction "1_1") (pintype "passive"))
      (node (ref "R33") (pin "1") (pinfunction "1_1") (pintype "passive"))
      (node (ref "R36") (pin "1") (pinfunction "1_1") (pintype "passive"))
      (node (ref "R38") (pin "1") (pinfunction "1_1") (pintype "passive"))
      (node (ref "R39") (pin "1") (pinfunction "1_1") (pintype "passive"))
      (node (ref "R5") (pin "1") (pinfunction "1_1") (pintype "passive"))
      (node (ref "R9") (pin "1") (pinfunction "1_1") (pintype "passive"))
      (node (ref "X1") (pin "GND") (pinfunction "GND_GND") (pintype "bidirectional"))
      (node (ref "X1") (pin "GND@1") (pinfunction "GND_GND@1") (pintype "bidirectional"))
      (node (ref "X1") (pin "GND@10") (pinfunction "GND_GND@10") (pintype "bidirectional"))
      (node (ref "X1") (pin "GND@11") (pinfunction "GND_GND@11") (pintype "bidirectional"))
      (node (ref "X1") (pin "GND@12") (pinfunction "GND_GND@12") (pintype "bidirectional"))
      (node (ref "X1") (pin "GND@13") (pinfunction "GND_GND@13") (pintype "bidirectional"))
      (node (ref "X1") (pin "GND@2") (pinfunction "GND_GND@2") (pintype "bidirectional"))
      (node (ref "X1") (pin "GND@3") (pinfunction "GND_GND@3") (pintype "bidirectional"))
      (node (ref "X1") (pin "GND@4") (pinfunction "GND_GND@4") (pintype "bidirectional"))
      (node (ref "X1") (pin "GND@5") (pinfunction "GND_GND@5") (pintype "bidirectional"))
      (node (ref "X1") (pin "GND@6") (pinfunction "GND_GND@6") (pintype "bidirectional"))
      (node (ref "X1") (pin "GND@7") (pinfunction "GND_GND@7") (pintype "bidirectional"))
      (node (ref "X1") (pin "GND@8") (pinfunction "GND_GND@8") (pintype "bidirectional"))
      (node (ref "X1") (pin "GND@9") (pinfunction "GND_GND@9") (pintype "bidirectional"))
      (node (ref "X10") (pin "1") (pinfunction "S_1") (pintype "passive"))
      (node (ref "X2") (pin "1") (pinfunction "S_1") (pintype "passive"))
      (node (ref "X3") (pin "2") (pinfunction "S_2") (pintype "passive"))
      (node (ref "X4") (pin "2") (pinfunction "S_2") (pintype "passive"))
      (node (ref "X5") (pin "1") (pinfunction "S_1") (pintype "passive"))
      (node (ref "X6") (pin "1") (pinfunction "S_1") (pintype "passive"))
      (node (ref "X7") (pin "1") (pinfunction "S_1") (pintype "passive"))
      (node (ref "X8") (pin "1") (pinfunction "S_1") (pintype "passive"))
      (node (ref "X9") (pin "1") (pinfunction "S_1") (pintype "passive"))
    )
    (net (code "49") (name "Net-(D4-PadC)") (class "Default")
      (node (ref "D4") (pin "C") (pinfunction "C_C") (pintype "passive"))
      (node (ref "R39") (pin "2") (pinfunction "2_2") (pintype "passive"))
    )
    (net (code "50") (name "Net-(IC1-ENU)") (class "Default")
      (node (ref "IC1") (pin "12") (pinfunction "ENW_12") (pintype "bidirectional"))
      (node (ref "IC1") (pin "16") (pinfunction "ENV_16") (pintype "bidirectional"))
      (node (ref "IC1") (pin "2") (pinfunction "ENU_2") (pintype "bidirectional"))
      (node (ref "R1") (pin "2") (pinfunction "2_2") (pintype "passive"))
      (node (ref "R2") (pin "2") (pinfunction "2_2") (pintype "passive"))
    )
    (net (code "51") (name "Net-(IC1-OUTU)") (class "Default")
      (node (ref "IC1") (pin "3") (pinfunction "OUTU_3") (pintype "bidirectional"))
      (node (ref "J1") (pin "1") (pinfunction "1_1") (pintype "passive"))
    )
    (net (code "52") (name "Net-(IC1-OUTV)") (class "Default")
      (node (ref "IC1") (pin "7") (pinfunction "OUTV_7") (pintype "bidirectional"))
      (node (ref "J1") (pin "2") (pinfunction "2_2") (pintype "passive"))
    )
    (net (code "53") (name "Net-(IC1-OUTW)") (class "Default")
      (node (ref "IC1") (pin "10") (pinfunction "OUTW_10") (pintype "bidirectional"))
      (node (ref "J1") (pin "3") (pinfunction "3_3") (pintype "passive"))
    )
    (net (code "54") (name "Net-(IC1-SENSEU)") (class "Default")
      (node (ref "IC1") (pin "4") (pinfunction "SENSEU_4") (pintype "bidirectional"))
      (node (ref "IC1") (pin "8") (pinfunction "SENSEV_8") (pintype "bidirectional"))
      (node (ref "IC1") (pin "9") (pinfunction "SENSEW_9") (pintype "bidirectional"))
      (node (ref "R5") (pin "2") (pinfunction "2_2") (pintype "passive"))
      (node (ref "R6") (pin "1") (pinfunction "1_1") (pintype "passive"))
    )
    (net (code "55") (name "Net-(IC1-STBY{slash}RESET)") (class "Default")
      (node (ref "C1") (pin "2") (pinfunction "2_2") (pintype "passive"))
      (node (ref "IC1") (pin "14") (pinfunction "STBY/RESET_14") (pintype "bidirectional"))
      (node (ref "R3") (pin "1") (pinfunction "1_1") (pintype "passive"))
    )
    (net (code "56") (name "Net-(IC2-ENU)") (class "Default")
      (node (ref "IC2") (pin "12") (pinfunction "ENW_12") (pintype "bidirectional"))
      (node (ref "IC2") (pin "16") (pinfunction "ENV_16") (pintype "bidirectional"))
      (node (ref "IC2") (pin "2") (pinfunction "ENU_2") (pintype "bidirectional"))
      (node (ref "R8") (pin "2") (pinfunction "2_2") (pintype "passive"))
      (node (ref "R9") (pin "2") (pinfunction "2_2") (pintype "passive"))
    )
    (net (code "57") (name "Net-(IC2-OUTU)") (class "Default")
      (node (ref "IC2") (pin "3") (pinfunction "OUTU_3") (pintype "bidirectional"))
      (node (ref "J2") (pin "1") (pinfunction "1_1") (pintype "passive"))
    )
    (net (code "58") (name "Net-(IC2-OUTV)") (class "Default")
      (node (ref "IC2") (pin "7") (pinfunction "OUTV_7") (pintype "bidirectional"))
      (node (ref "J2") (pin "2") (pinfunction "2_2") (pintype "passive"))
    )
    (net (code "59") (name "Net-(IC2-OUTW)") (class "Default")
      (node (ref "IC2") (pin "10") (pinfunction "OUTW_10") (pintype "bidirectional"))
      (node (ref "J2") (pin "3") (pinfunction "3_3") (pintype "passive"))
    )
    (net (code "60") (name "Net-(IC2-SENSEU)") (class "Default")
      (node (ref "IC2") (pin "4") (pinfunction "SENSEU_4") (pintype "bidirectional"))
      (node (ref "IC2") (pin "8") (pinfunction "SENSEV_8") (pintype "bidirectional"))
      (node (ref "IC2") (pin "9") (pinfunction "SENSEW_9") (pintype "bidirectional"))
      (node (ref "R12") (pin "2") (pinfunction "2_2") (pintype "passive"))
      (node (ref "R13") (pin "1") (pinfunction "1_1") (pintype "passive"))
    )
    (net (code "61") (name "Net-(IC2-STBY{slash}RESET)") (class "Default")
      (node (ref "C6") (pin "2") (pinfunction "2_2") (pintype "passive"))
      (node (ref "IC2") (pin "14") (pinfunction "STBY/RESET_14") (pintype "bidirectional"))
      (node (ref "R10") (pin "1") (pinfunction "1_1") (pintype "passive"))
    )
    (net (code "62") (name "Net-(IC3-ENU)") (class "Default")
      (node (ref "IC3") (pin "12") (pinfunction "ENW_12") (pintype "bidirectional"))
      (node (ref "IC3") (pin "16") (pinfunction "ENV_16") (pintype "bidirectional"))
      (node (ref "IC3") (pin "2") (pinfunction "ENU_2") (pintype "bidirectional"))
      (node (ref "R15") (pin "2") (pinfunction "2_2") (pintype "passive"))
      (node (ref "R16") (pin "2") (pinfunction "2_2") (pintype "passive"))
    )
    (net (code "63") (name "Net-(IC3-OUTU)") (class "Default")
      (node (ref "IC3") (pin "3") (pinfunction "OUTU_3") (pintype "bidirectional"))
      (node (ref "J3") (pin "1") (pinfunction "1_1") (pintype "passive"))
    )
    (net (code "64") (name "Net-(IC3-OUTV)") (class "Default")
      (node (ref "IC3") (pin "7") (pinfunction "OUTV_7") (pintype "bidirectional"))
      (node (ref "J3") (pin "2") (pinfunction "2_2") (pintype "passive"))
    )
    (net (code "65") (name "Net-(IC3-OUTW)") (class "Default")
      (node (ref "IC3") (pin "10") (pinfunction "OUTW_10") (pintype "bidirectional"))
      (node (ref "J3") (pin "3") (pinfunction "3_3") (pintype "passive"))
    )
    (net (code "66") (name "Net-(IC3-SENSEU)") (class "Default")
      (node (ref "IC3") (pin "4") (pinfunction "SENSEU_4") (pintype "bidirectional"))
      (node (ref "IC3") (pin "8") (pinfunction "SENSEV_8") (pintype "bidirectional"))
      (node (ref "IC3") (pin "9") (pinfunction "SENSEW_9") (pintype "bidirectional"))
      (node (ref "R19") (pin "2") (pinfunction "2_2") (pintype "passive"))
      (node (ref "R20") (pin "1") (pinfunction "1_1") (pintype "passive"))
    )
    (net (code "67") (name "Net-(IC3-STBY{slash}RESET)") (class "Default")
      (node (ref "C11") (pin "2") (pinfunction "2_2") (pintype "passive"))
      (node (ref "IC3") (pin "14") (pinfunction "STBY/RESET_14") (pintype "bidirectional"))
      (node (ref "R17") (pin "1") (pinfunction "1_1") (pintype "passive"))
    )
    (net (code "68") (name "Net-(IC4-ENU)") (class "Default")
      (node (ref "IC4") (pin "12") (pinfunction "ENW_12") (pintype "bidirectional"))
      (node (ref "IC4") (pin "16") (pinfunction "ENV_16") (pintype "bidirectional"))
      (node (ref "IC4") (pin "2") (pinfunction "ENU_2") (pintype "bidirectional"))
      (node (ref "R22") (pin "2") (pinfunction "2_2") (pintype "passive"))
      (node (ref "R23") (pin "2") (pinfunction "2_2") (pintype "passive"))
    )
    (net (code "69") (name "Net-(IC4-OUTU)") (class "Default")
      (node (ref "IC4") (pin "3") (pinfunction "OUTU_3") (pintype "bidirectional"))
      (node (ref "J4") (pin "1") (pinfunction "1_1") (pintype "passive"))
    )
    (net (code "70") (name "Net-(IC4-OUTV)") (class "Default")
      (node (ref "IC4") (pin "7") (pinfunction "OUTV_7") (pintype "bidirectional"))
      (node (ref "J4") (pin "2") (pinfunction "2_2") (pintype "passive"))
    )
    (net (code "71") (name "Net-(IC4-OUTW)") (class "Default")
      (node (ref "IC4") (pin "10") (pinfunction "OUTW_10") (pintype "bidirectional"))
      (node (ref "J4") (pin "3") (pinfunction "3_3") (pintype "passive"))
    )
    (net (code "72") (name "Net-(IC4-SENSEU)") (class "Default")
      (node (ref "IC4") (pin "4") (pinfunction "SENSEU_4") (pintype "bidirectional"))
      (node (ref "IC4") (pin "8") (pinfunction "SENSEV_8") (pintype "bidirectional"))
      (node (ref "IC4") (pin "9") (pinfunction "SENSEW_9") (pintype "bidirectional"))
      (node (ref "R26") (pin "2") (pinfunction "2_2") (pintype "passive"))
      (node (ref "R27") (pin "1") (pinfunction "1_1") (pintype "passive"))
    )
    (net (code "73") (name "Net-(IC4-STBY{slash}RESET)") (class "Default")
      (node (ref "C16") (pin "2") (pinfunction "2_2") (pintype "passive"))
      (node (ref "IC4") (pin "14") (pinfunction "STBY/RESET_14") (pintype "bidirectional"))
      (node (ref "R24") (pin "1") (pinfunction "1_1") (pintype "passive"))
    )
    (net (code "74") (name "Net-(IC5-ENU)") (class "Default")
      (node (ref "IC5") (pin "12") (pinfunction "ENW_12") (pintype "bidirectional"))
      (node (ref "IC5") (pin "16") (pinfunction "ENV_16") (pintype "bidirectional"))
      (node (ref "IC5") (pin "2") (pinfunction "ENU_2") (pintype "bidirectional"))
      (node (ref "R29") (pin "2") (pinfunction "2_2") (pintype "passive"))
      (node (ref "R30") (pin "2") (pinfunction "2_2") (pintype "passive"))
    )
    (net (code "75") (name "Net-(IC5-OUTU)") (class "Default")
      (node (ref "IC5") (pin "3") (pinfunction "OUTU_3") (pintype "bidirectional"))
      (node (ref "J5") (pin "1") (pinfunction "1_1") (pintype "passive"))
    )
    (net (code "76") (name "Net-(IC5-OUTV)") (class "Default")
      (node (ref "IC5") (pin "7") (pinfunction "OUTV_7") (pintype "bidirectional"))
      (node (ref "J5") (pin "2") (pinfunction "2_2") (pintype "passive"))
    )
    (net (code "77") (name "Net-(IC5-OUTW)") (class "Default")
      (node (ref "IC5") (pin "10") (pinfunction "OUTW_10") (pintype "bidirectional"))
      (node (ref "J5") (pin "3") (pinfunction "3_3") (pintype "passive"))
    )
    (net (code "78") (name "Net-(IC5-SENSEU)") (class "Default")
      (node (ref "IC5") (pin "4") (pinfunction "SENSEU_4") (pintype "bidirectional"))
      (node (ref "IC5") (pin "8") (pinfunction "SENSEV_8") (pintype "bidirectional"))
      (node (ref "IC5") (pin "9") (pinfunction "SENSEW_9") (pintype "bidirectional"))
      (node (ref "R33") (pin "2") (pinfunction "2_2") (pintype "passive"))
      (node (ref "R34") (pin "1") (pinfunction "1_1") (pintype "passive"))
    )
    (net (code "79") (name "Net-(IC5-STBY{slash}RESET)") (class "Default")
      (node (ref "C21") (pin "2") (pinfunction "2_2") (pintype "passive"))
      (node (ref "IC5") (pin "14") (pinfunction "STBY/RESET_14") (pintype "bidirectional"))
      (node (ref "R31") (pin "1") (pinfunction "1_1") (pintype "passive"))
    )
    (net (code "80") (name "Net-(IC6-BOOT)") (class "Default")
      (node (ref "C31") (pin "1") (pinfunction "1_1") (pintype "passive"))
      (node (ref "IC6") (pin "4") (pinfunction "BOOT_4") (pintype "bidirectional"))
    )
    (net (code "81") (name "Net-(IC6-EN)") (class "Default")
      (node (ref "C26") (pin "1") (pinfunction "1_1") (pintype "passive"))
      (node (ref "C29") (pin "1") (pinfunction "1_1") (pintype "passive"))
      (node (ref "C30") (pin "1") (pinfunction "1_1") (pintype "passive"))
      (node (ref "D1") (pin "C") (pinfunction "C_C") (pintype "passive"))
      (node (ref "D2") (pin "C") (pinfunction "C_C") (pintype "passive"))
      (node (ref "D3") (pin "C") (pinfunction "C_C") (pintype "passive"))
      (node (ref "IC6") (pin "10") (pinfunction "VIN_1_10") (pintype "bidirectional"))
      (node (ref "IC6") (pin "11") (pinfunction "VIN_2_11") (pintype "bidirectional"))
      (node (ref "IC6") (pin "12") (pinfunction "VIN_3_12") (pintype "bidirectional"))
      (node (ref "IC6") (pin "9") (pinfunction "EN_9") (pintype "bidirectional"))
    )
    (net (code "82") (name "Net-(IC6-FB)") (class "Default")
      (node (ref "IC6") (pin "7") (pinfunction "FB_7") (pintype "bidirectional"))
      (node (ref "R37") (pin "1") (pinfunction "1_1") (pintype "passive"))
      (node (ref "R38") (pin "2") (pinfunction "2_2") (pintype "passive"))
    )
    (net (code "83") (name "Net-(IC6-RT)") (class "Default")
      (node (ref "IC6") (pin "6") (pinfunction "RT_6") (pintype "bidirectional"))
      (node (ref "R36") (pin "2") (pinfunction "2_2") (pintype "passive"))
    )
    (net (code "84") (name "Net-(IC6-SW_1)") (class "Default")
      (node (ref "C31") (pin "2") (pinfunction "2_2") (pintype "passive"))
      (node (ref "IC6") (pin "1") (pinfunction "SW_1_1") (pintype "bidirectional"))
      (node (ref "IC6") (pin "2") (pinfunction "SW_2_2") (pintype "bidirectional"))
      (node (ref "IC6") (pin "3") (pinfunction "SW_3_3") (pintype "bidirectional"))
      (node (ref "L1") (pin "1") (pinfunction "1_1") (pintype "bidirectional"))
    )
    (net (code "85") (name "Net-(X1-67-Pad67@1)") (class "Default")
      (node (ref "X1") (pin "67") (pinfunction "67_67") (pintype "bidirectional"))
      (node (ref "X1") (pin "67@1") (pinfunction "67_67@1") (pintype "bidirectional"))
    )
    (net (code "86") (name "Net-(X1-~{RESET}-Pad!RESET)") (class "Default")
      (node (ref "X1") (pin "!RESET") (pinfunction "~{RESET}_!RESET") (pintype "bidirectional"))
      (node (ref "X1") (pin "RESET") (pinfunction "~{RESET}_RESET") (pintype "bidirectional"))
    )
    (net (code "87") (name "Net-(X3A-S)") (class "Default")
      (node (ref "D3") (pin "A") (pinfunction "A_A") (pintype "passive"))
      (node (ref "X3") (pin "1") (pinfunction "S_1") (pintype "passive"))
    )
    (net (code "88") (name "Net-(X4A-S)") (class "Default")
      (node (ref "D2") (pin "A") (pinfunction "A_A") (pintype "passive"))
      (node (ref "X4") (pin "1") (pinfunction "S_1") (pintype "passive"))
    )
    (net (code "89") (name "unconnected-(IC6-PG-Pad5)") (class "Default")
      (node (ref "IC6") (pin "5") (pinfunction "PG_5") (pintype "bidirectional"))
    )
    (net (code "90") (name "unconnected-(X1-Pad19)") (class "Default")
      (node (ref "X1") (pin "19") (pinfunction "19_19") (pintype "bidirectional"))
    )
    (net (code "91") (name "unconnected-(X1-Pad22)") (class "Default")
      (node (ref "X1") (pin "22") (pinfunction "22_22") (pintype "bidirectional"))
    )
    (net (code "92") (name "unconnected-(X1-Pad23)") (class "Default")
      (node (ref "X1") (pin "23") (pinfunction "23_23") (pintype "bidirectional"))
    )
    (net (code "93") (name "unconnected-(X1-Pad24)") (class "Default")
      (node (ref "X1") (pin "24") (pinfunction "24_24") (pintype "bidirectional"))
    )
    (net (code "94") (name "unconnected-(X1-Pad25)") (class "Default")
      (node (ref "X1") (pin "25") (pinfunction "25_25") (pintype "bidirectional"))
    )
    (net (code "95") (name "unconnected-(X1-Pad26)") (class "Default")
      (node (ref "X1") (pin "26") (pinfunction "26_26") (pintype "bidirectional"))
    )
    (net (code "96") (name "unconnected-(X1-Pad27)") (class "Default")
      (node (ref "X1") (pin "27") (pinfunction "27_27") (pintype "bidirectional"))
    )
    (net (code "97") (name "unconnected-(X1-Pad28)") (class "Default")
      (node (ref "X1") (pin "28") (pinfunction "28_28") (pintype "bidirectional"))
    )
    (net (code "98") (name "unconnected-(X1-Pad29)") (class "Default")
      (node (ref "X1") (pin "29") (pinfunction "29_29") (pintype "bidirectional"))
    )
    (net (code "99") (name "unconnected-(X1-Pad30)") (class "Default")
      (node (ref "X1") (pin "30") (pinfunction "30_30") (pintype "bidirectional"))
    )
    (net (code "100") (name "unconnected-(X1-Pad31)") (class "Default")
      (node (ref "X1") (pin "31") (pinfunction "31_31") (pintype "bidirectional"))
    )
    (net (code "101") (name "unconnected-(X1-Pad32)") (class "Default")
      (node (ref "X1") (pin "32") (pinfunction "32_32") (pintype "bidirectional"))
    )
    (net (code "102") (name "unconnected-(X1-Pad33)") (class "Default")
      (node (ref "X1") (pin "33") (pinfunction "33_33") (pintype "bidirectional"))
    )
    (net (code "103") (name "unconnected-(X1-Pad34)") (class "Default")
      (node (ref "X1") (pin "34") (pinfunction "34_34") (pintype "bidirectional"))
    )
    (net (code "104") (name "unconnected-(X1-Pad35)") (class "Default")
      (node (ref "X1") (pin "35") (pinfunction "35_35") (pintype "bidirectional"))
    )
    (net (code "105") (name "unconnected-(X1-Pad36)") (class "Default")
      (node (ref "X1") (pin "36") (pinfunction "36_36") (pintype "bidirectional"))
    )
    (net (code "106") (name "unconnected-(X1-Pad37)") (class "Default")
      (node (ref "X1") (pin "37") (pinfunction "37_37") (pintype "bidirectional"))
    )
    (net (code "107") (name "unconnected-(X1-Pad38)") (class "Default")
      (node (ref "X1") (pin "38") (pinfunction "38_38") (pintype "bidirectional"))
    )
    (net (code "108") (name "unconnected-(X1-Pad39)") (class "Default")
      (node (ref "X1") (pin "39") (pinfunction "39_39") (pintype "bidirectional"))
    )
    (net (code "109") (name "unconnected-(X1-Pad40)") (class "Default")
      (node (ref "X1") (pin "40") (pinfunction "40_40") (pintype "bidirectional"))
    )
    (net (code "110") (name "unconnected-(X1-Pad41)") (class "Default")
      (node (ref "X1") (pin "41") (pinfunction "41_41") (pintype "bidirectional"))
    )
    (net (code "111") (name "unconnected-(X1-Pad42)") (class "Default")
      (node (ref "X1") (pin "42") (pinfunction "42_42") (pintype "bidirectional"))
    )
    (net (code "112") (name "unconnected-(X1-Pad43)") (class "Default")
      (node (ref "X1") (pin "43") (pinfunction "43_43") (pintype "bidirectional"))
    )
    (net (code "113") (name "unconnected-(X1-Pad44)") (class "Default")
      (node (ref "X1") (pin "44") (pinfunction "44_44") (pintype "bidirectional"))
    )
    (net (code "114") (name "unconnected-(X1-Pad45)") (class "Default")
      (node (ref "X1") (pin "45") (pinfunction "45_45") (pintype "bidirectional"))
    )
    (net (code "115") (name "unconnected-(X1-Pad46)") (class "Default")
      (node (ref "X1") (pin "46") (pinfunction "46_46") (pintype "bidirectional"))
    )
    (net (code "116") (name "unconnected-(X1-Pad47)") (class "Default")
      (node (ref "X1") (pin "47") (pinfunction "47_47") (pintype "bidirectional"))
    )
    (net (code "117") (name "unconnected-(X1-Pad49)") (class "Default")
      (node (ref "X1") (pin "49") (pinfunction "49_49") (pintype "bidirectional"))
    )
    (net (code "118") (name "unconnected-(X1-Pad50)") (class "Default")
      (node (ref "X1") (pin "50") (pinfunction "50_50") (pintype "bidirectional"))
    )
    (net (code "119") (name "unconnected-(X1-Pad51)") (class "Default")
      (node (ref "X1") (pin "51") (pinfunction "51_51") (pintype "bidirectional"))
    )
    (net (code "120") (name "unconnected-(X1-Pad52)") (class "Default")
      (node (ref "X1") (pin "52") (pinfunction "52_52") (pintype "bidirectional"))
    )
    (net (code "121") (name "unconnected-(X1-Pad53)") (class "Default")
      (node (ref "X1") (pin "53") (pinfunction "53_53") (pintype "bidirectional"))
    )
    (net (code "122") (name "unconnected-(X1-Pad54)") (class "Default")
      (node (ref "X1") (pin "54") (pinfunction "54_54") (pintype "bidirectional"))
    )
    (net (code "123") (name "unconnected-(X1-Pad55)") (class "Default")
      (node (ref "X1") (pin "55") (pinfunction "55_55") (pintype "bidirectional"))
    )
    (net (code "124") (name "unconnected-(X1-Pad59)") (class "Default")
      (node (ref "X1") (pin "59") (pinfunction "59_59") (pintype "bidirectional"))
    )
    (net (code "125") (name "unconnected-(X1-Pad61)") (class "Default")
      (node (ref "X1") (pin "61") (pinfunction "61_61") (pintype "bidirectional"))
    )
    (net (code "126") (name "unconnected-(X1-Pad63)") (class "Default")
      (node (ref "X1") (pin "63") (pinfunction "63_63") (pintype "bidirectional"))
    )
    (net (code "127") (name "unconnected-(X1-Pad65)") (class "Default")
      (node (ref "X1") (pin "65") (pinfunction "65_65") (pintype "bidirectional"))
    )
    (net (code "128") (name "unconnected-(X1-Pad68)") (class "Default")
      (node (ref "X1") (pin "68") (pinfunction "68_68") (pintype "bidirectional"))
    )
    (net (code "129") (name "unconnected-(X1-Pad69)") (class "Default")
      (node (ref "X1") (pin "69") (pinfunction "69_69") (pintype "bidirectional"))
    )
    (net (code "130") (name "unconnected-(X1-Pad70)") (class "Default")
      (node (ref "X1") (pin "70") (pinfunction "70_70") (pintype "bidirectional"))
    )
    (net (code "131") (name "unconnected-(X1-Pad71)") (class "Default")
      (node (ref "X1") (pin "71") (pinfunction "71_71") (pintype "bidirectional"))
    )
    (net (code "132") (name "unconnected-(X1-Pad72)") (class "Default")
      (node (ref "X1") (pin "72") (pinfunction "72_72") (pintype "bidirectional"))
    )
    (net (code "133") (name "unconnected-(X1-Pad73)") (class "Default")
      (node (ref "X1") (pin "73") (pinfunction "73_73") (pintype "bidirectional"))
    )
    (net (code "134") (name "unconnected-(X1-Pad74)") (class "Default")
      (node (ref "X1") (pin "74") (pinfunction "74_74") (pintype "bidirectional"))
    )
    (net (code "135") (name "unconnected-(X1-Pad75)") (class "Default")
      (node (ref "X1") (pin "75") (pinfunction "75_75") (pintype "bidirectional"))
    )
    (net (code "136") (name "unconnected-(X1-PadA8)") (class "Default")
      (node (ref "X1") (pin "A8") (pinfunction "A8_A8") (pintype "bidirectional"))
    )
    (net (code "137") (name "unconnected-(X1-PadA9)") (class "Default")
      (node (ref "X1") (pin "A9") (pinfunction "A9_A9") (pintype "bidirectional"))
    )
    (net (code "138") (name "unconnected-(X1-PadA10)") (class "Default")
      (node (ref "X1") (pin "A10") (pinfunction "A10_A10") (pintype "bidirectional"))
    )
    (net (code "139") (name "unconnected-(X1-PadA11)") (class "Default")
      (node (ref "X1") (pin "A11") (pinfunction "A11_A11") (pintype "bidirectional"))
    )
    (net (code "140") (name "unconnected-(X1-PadAREF)") (class "Default")
      (node (ref "X1") (pin "AREF") (pinfunction "AREF_AREF") (pintype "bidirectional"))
    )
    (net (code "141") (name "unconnected-(X1-PadCKN)") (class "Default")
      (node (ref "X1") (pin "CKN") (pinfunction "CKN_CKN") (pintype "bidirectional"))
    )
    (net (code "142") (name "unconnected-(X1-PadCKP)") (class "Default")
      (node (ref "X1") (pin "CKP") (pinfunction "CKP_CKP") (pintype "bidirectional"))
    )
    (net (code "143") (name "unconnected-(X1-PadD0N)") (class "Default")
      (node (ref "X1") (pin "D0N") (pinfunction "D0N_D0N") (pintype "bidirectional"))
    )
    (net (code "144") (name "unconnected-(X1-PadD0P)") (class "Default")
      (node (ref "X1") (pin "D0P") (pinfunction "D0P_D0P") (pintype "bidirectional"))
    )
    (net (code "145") (name "unconnected-(X1-PadD1N)") (class "Default")
      (node (ref "X1") (pin "D1N") (pinfunction "D1N_D1N") (pintype "bidirectional"))
    )
    (net (code "146") (name "unconnected-(X1-PadD1P)") (class "Default")
      (node (ref "X1") (pin "D1P") (pinfunction "D1P_D1P") (pintype "bidirectional"))
    )
    (net (code "147") (name "unconnected-(X1-PadIOREF)") (class "Default")
      (node (ref "X1") (pin "IOREF") (pinfunction "IOREF_IOREF") (pintype "bidirectional"))
    )
    (net (code "148") (name "unconnected-(X1-SCL-Pad21)") (class "Default")
      (node (ref "X1") (pin "21") (pinfunction "SCL_21") (pintype "bidirectional"))
    )
    (net (code "149") (name "unconnected-(X1-SDA-Pad20)") (class "Default")
      (node (ref "X1") (pin "20") (pinfunction "SDA_20") (pintype "bidirectional"))
    )
  )
)
